# PowerDomain.net
KiCad netlist of a schematic drawn in Altium Designer
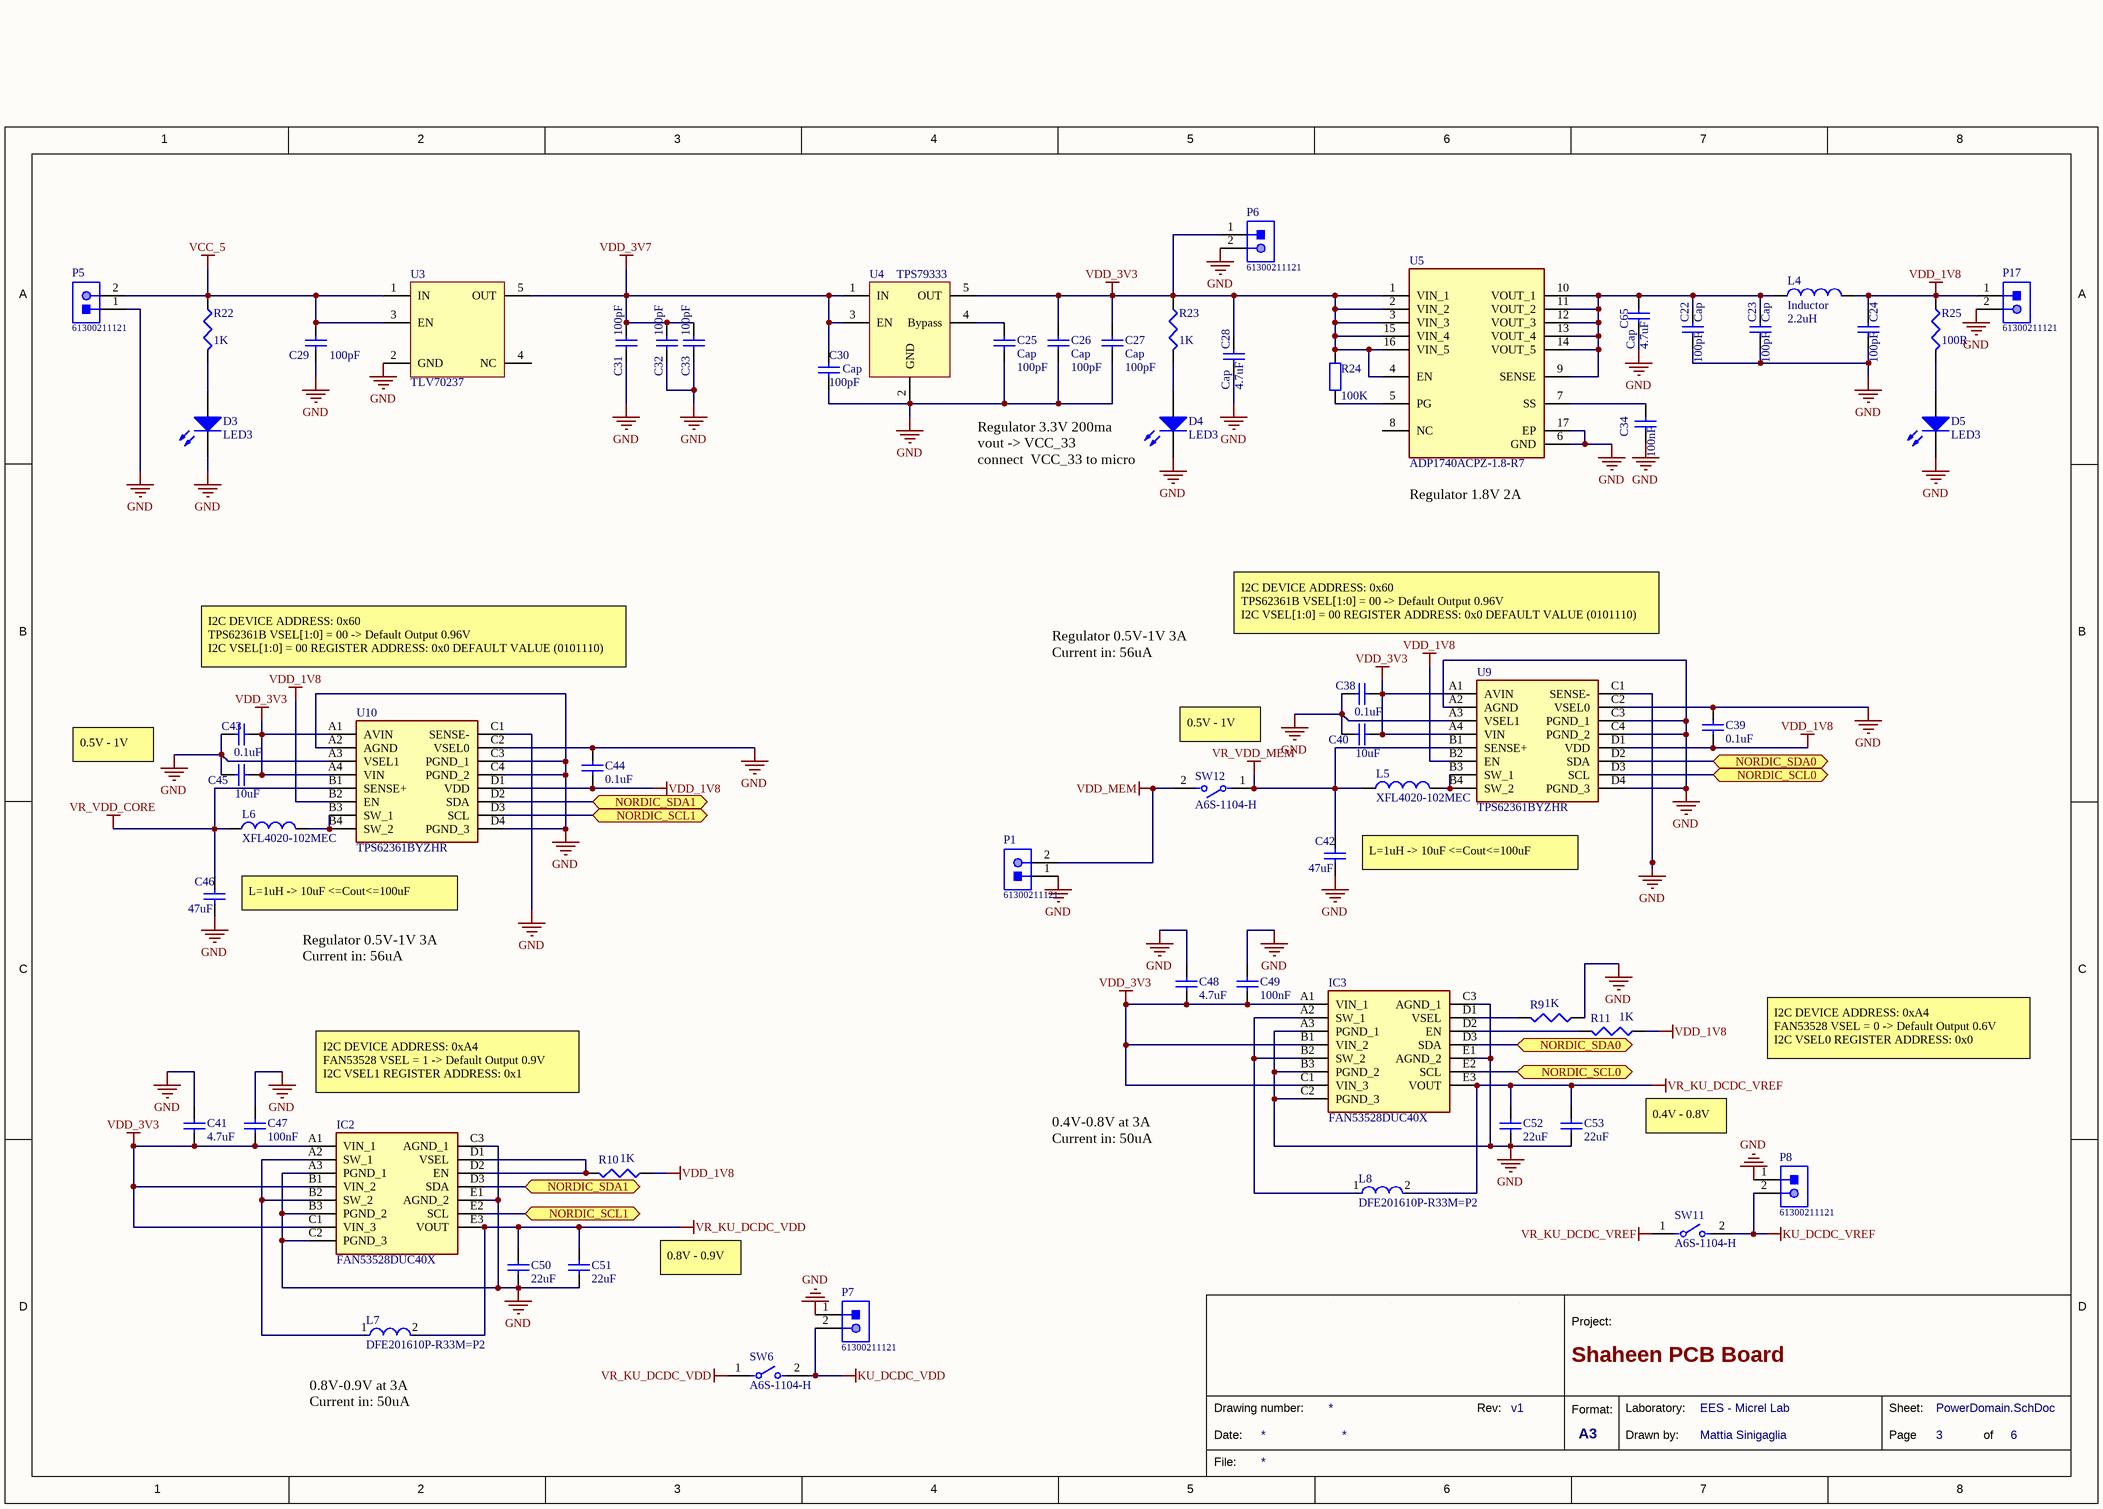
[diagram p0: PowerDomain.SchDoc]

(export (version "E")
  (design (tool "Eeschema 10.0.6"))
  (components
    (comp (ref "C22")
      (value "Cap")
      (footprint "0603")
      (description "Capacitor")
      (fields (field (name "ALTIUM_VALUE") "100pF") (field (name "PUBLISHER") "Altium Limited"))
      (libsource (lib "Miscellaneous Devices") (part "Cap"))
    )
    (comp (ref "C23")
      (value "Cap")
      (footprint "0603")
      (description "Capacitor")
      (fields (field (name "ALTIUM_VALUE") "100pF") (field (name "PUBLISHER") "Altium Limited"))
      (libsource (lib "Miscellaneous Devices") (part "Cap"))
    )
    (comp (ref "C24")
      (value "100pF")
      (footprint "0603")
      (description "Capacitor")
      (fields (field (name "Comment") "Cap") (field (name "PUBLISHER") "Altium Limited"))
      (libsource (lib "Miscellaneous Devices") (part "Cap"))
    )
    (comp (ref "C25")
      (value "Cap")
      (footprint "cap_0402_R - modified")
      (description "Capacitor")
      (fields (field (name "ALTIUM_VALUE") "100pF") (field (name "PUBLISHER") "Altium Limited"))
      (libsource (lib "Miscellaneous Devices") (part "Cap"))
    )
    (comp (ref "C26")
      (value "Cap")
      (footprint "cap_0402_R - modified")
      (description "Capacitor")
      (fields (field (name "ALTIUM_VALUE") "100pF") (field (name "PUBLISHER") "Altium Limited"))
      (libsource (lib "Miscellaneous Devices") (part "Cap"))
    )
    (comp (ref "C27")
      (value "Cap")
      (footprint "cap_0402_R - modified")
      (description "Capacitor")
      (fields (field (name "ALTIUM_VALUE") "100pF") (field (name "PUBLISHER") "Altium Limited"))
      (libsource (lib "Miscellaneous Devices") (part "Cap"))
    )
    (comp (ref "C28")
      (value "Cap")
      (footprint "0603")
      (description "Capacitor")
      (fields (field (name "ALTIUM_VALUE") "4.7uF") (field (name "PUBLISHER") "Altium Limited"))
      (libsource (lib "Miscellaneous Devices") (part "Cap"))
    )
    (comp (ref "C29")
      (value "100pF")
      (footprint "1608[0603]")
      (description "Capacitor (Semiconductor SIM Model)")
      (fields (field (name "Comment") "Cap Semi") (field (name "PUBLISHER") "Altium Limited"))
      (libsource (lib "Miscellaneous Devices") (part "Cap Semi"))
    )
    (comp (ref "C30")
      (value "Cap")
      (footprint "cap_0402_R - modified")
      (description "Capacitor")
      (fields (field (name "ALTIUM_VALUE") "100pF") (field (name "PUBLISHER") "Altium Limited"))
      (libsource (lib "Miscellaneous Devices") (part "Cap"))
    )
    (comp (ref "C31")
      (value "100pF")
      (footprint "1608[0603]")
      (description "Capacitor (Semiconductor SIM Model)")
      (fields (field (name "Comment") "Cap Semi") (field (name "PUBLISHER") "Altium Limited"))
      (libsource (lib "Miscellaneous Devices") (part "Cap Semi"))
    )
    (comp (ref "C32")
      (value "100pF")
      (footprint "1608[0603]")
      (description "Capacitor (Semiconductor SIM Model)")
      (fields (field (name "Comment") "Cap Semi") (field (name "PUBLISHER") "Altium Limited"))
      (libsource (lib "Miscellaneous Devices") (part "Cap Semi"))
    )
    (comp (ref "C33")
      (value "100pF")
      (footprint "1608[0603]")
      (description "Capacitor (Semiconductor SIM Model)")
      (fields (field (name "Comment") "Cap Semi") (field (name "PUBLISHER") "Altium Limited"))
      (libsource (lib "Miscellaneous Devices") (part "Cap Semi"))
    )
    (comp (ref "C34")
      (value "100nF")
      (footprint "0603")
      (description "Capacitor")
      (fields (field (name "PUBLISHER") "Altium Limited"))
      (libsource (lib "Miscellaneous Devices") (part "Cap"))
    )
    (comp (ref "C38")
      (value "0.1uF")
      (footprint "0603")
      (description "Capacitor")
      (fields (field (name "Comment") "Cap") (field (name "PUBLISHER") "Altium Limited"))
      (libsource (lib "Miscellaneous Devices") (part "Cap"))
    )
    (comp (ref "C39")
      (value "0.1uF")
      (footprint "0603")
      (description "Capacitor")
      (fields (field (name "Comment") "Cap") (field (name "PUBLISHER") "Altium Limited"))
      (libsource (lib "Miscellaneous Devices") (part "Cap"))
    )
    (comp (ref "C40")
      (value "10uF")
      (footprint "0603")
      (description "Capacitor")
      (fields (field (name "Comment") "Cap") (field (name "PUBLISHER") "Altium Limited"))
      (libsource (lib "Miscellaneous Devices") (part "Cap"))
    )
    (comp (ref "C41")
      (value "4.7uF")
      (footprint "0603")
      (description "Capacitor")
      (fields (field (name "Comment") "Cap") (field (name "PUBLISHER") "Altium Limited"))
      (libsource (lib "Miscellaneous Devices") (part "Cap"))
    )
    (comp (ref "C42")
      (value "47uF")
      (footprint "0603")
      (description "Capacitor")
      (fields (field (name "Comment") "Cap") (field (name "PUBLISHER") "Altium Limited"))
      (libsource (lib "Miscellaneous Devices") (part "Cap"))
    )
    (comp (ref "C43")
      (value "0.1uF")
      (footprint "0603")
      (description "Capacitor")
      (fields (field (name "Comment") "Cap") (field (name "PUBLISHER") "Altium Limited"))
      (libsource (lib "Miscellaneous Devices") (part "Cap"))
    )
    (comp (ref "C44")
      (value "0.1uF")
      (footprint "0603")
      (description "Capacitor")
      (fields (field (name "Comment") "Cap") (field (name "PUBLISHER") "Altium Limited"))
      (libsource (lib "Miscellaneous Devices") (part "Cap"))
    )
    (comp (ref "C45")
      (value "10uF")
      (footprint "0603")
      (description "Capacitor")
      (fields (field (name "Comment") "Cap") (field (name "PUBLISHER") "Altium Limited"))
      (libsource (lib "Miscellaneous Devices") (part "Cap"))
    )
    (comp (ref "C46")
      (value "47uF")
      (footprint "0603")
      (description "Capacitor")
      (fields (field (name "Comment") "Cap") (field (name "PUBLISHER") "Altium Limited"))
      (libsource (lib "Miscellaneous Devices") (part "Cap"))
    )
    (comp (ref "C47")
      (value "100nF")
      (footprint "0603")
      (description "Capacitor")
      (fields (field (name "Comment") "Cap") (field (name "PUBLISHER") "Altium Limited"))
      (libsource (lib "Miscellaneous Devices") (part "Cap"))
    )
    (comp (ref "C48")
      (value "4.7uF")
      (footprint "0603")
      (description "Capacitor")
      (fields (field (name "Comment") "Cap") (field (name "PUBLISHER") "Altium Limited"))
      (libsource (lib "Miscellaneous Devices") (part "Cap"))
    )
    (comp (ref "C49")
      (value "100nF")
      (footprint "0603")
      (description "Capacitor")
      (fields (field (name "Comment") "Cap") (field (name "PUBLISHER") "Altium Limited"))
      (libsource (lib "Miscellaneous Devices") (part "Cap"))
    )
    (comp (ref "C50")
      (value "22uF")
      (footprint "0603")
      (description "Capacitor")
      (fields (field (name "Comment") "Cap") (field (name "PUBLISHER") "Altium Limited"))
      (libsource (lib "Miscellaneous Devices") (part "Cap"))
    )
    (comp (ref "C51")
      (value "22uF")
      (footprint "0603")
      (description "Capacitor")
      (fields (field (name "Comment") "Cap") (field (name "PUBLISHER") "Altium Limited"))
      (libsource (lib "Miscellaneous Devices") (part "Cap"))
    )
    (comp (ref "C52")
      (value "22uF")
      (footprint "0603")
      (description "Capacitor")
      (fields (field (name "Comment") "Cap") (field (name "PUBLISHER") "Altium Limited"))
      (libsource (lib "Miscellaneous Devices") (part "Cap"))
    )
    (comp (ref "C53")
      (value "22uF")
      (footprint "0603")
      (description "Capacitor")
      (fields (field (name "Comment") "Cap") (field (name "PUBLISHER") "Altium Limited"))
      (libsource (lib "Miscellaneous Devices") (part "Cap"))
    )
    (comp (ref "C65")
      (value "Cap")
      (footprint "0603")
      (description "Capacitor")
      (fields (field (name "ALTIUM_VALUE") "4.7uF") (field (name "PUBLISHER") "Altium Limited"))
      (libsource (lib "Miscellaneous Devices") (part "Cap"))
    )
    (comp (ref "D3")
      (value "LED3")
      (footprint "0603")
      (description "Typical BLUE SiC LED")
      (fields (field (name "PUBLISHER") "Altium Limited"))
      (libsource (lib "Miscellaneous Devices") (part "LED3"))
    )
    (comp (ref "D4")
      (value "LED3")
      (footprint "0603")
      (description "Typical BLUE SiC LED")
      (fields (field (name "PUBLISHER") "Altium Limited"))
      (libsource (lib "Miscellaneous Devices") (part "LED3"))
    )
    (comp (ref "D5")
      (value "LED3")
      (footprint "0603")
      (description "Typical BLUE SiC LED")
      (fields (field (name "PUBLISHER") "Altium Limited"))
      (libsource (lib "Miscellaneous Devices") (part "LED3"))
    )
    (comp (ref "IC2")
      (value "FAN53528DUC40X")
      (footprint "BGA15C40P3X5_131X202X62")
      (description "Integrated Circuit")
      (libsource (lib "FAN53528DUC40X") (part "FAN53528DUC40X"))
    )
    (comp (ref "IC3")
      (value "FAN53528DUC40X")
      (footprint "BGA15C40P3X5_131X202X62")
      (description "Integrated Circuit")
      (libsource (lib "FAN53528DUC40X") (part "FAN53528DUC40X"))
    )
    (comp (ref "L4")
      (value "Inductor")
      (footprint "Demo_Board_library_PCB:0603")
      (fields (field (name "ALTIUM_VALUE") "2.2uH") (field (name "PUBLISHER") "Altium Limited"))
      (libsource (lib "Miscellaneous Devices") (part "Inductor"))
    )
    (comp (ref "L5")
      (value "XFL4020-102MEC")
      (footprint "COIL-XFL4020_V")
      (description "Shielded Power Inductor, 1 uH, 64 MHz, -40 to 125 degC, 2-Pin SMD, RoHS, Tape and Reel")
      (fields (field (name "MANUFACTURER") "Coilcraft") (field (name "TOLERANCE") "20%"))
      (libsource (lib "Altium Content Vault") (part "IND-2"))
    )
    (comp (ref "L6")
      (value "XFL4020-102MEC")
      (footprint "COIL-XFL4020_V")
      (description "Shielded Power Inductor, 1 uH, 64 MHz, -40 to 125 degC, 2-Pin SMD, RoHS, Tape and Reel")
      (fields (field (name "MANUFACTURER") "Coilcraft") (field (name "TOLERANCE") "20%"))
      (libsource (lib "Altium Content Vault") (part "IND-2"))
    )
    (comp (ref "L7")
      (value "DFE201610P-R33M=P2")
      (footprint "FP-DFE201610C-MFG")
      (description "Shielded Wirewound Inductor 0.33uH 20% 3500mA 0.034Ω 0806 (2016)")
      (fields (field (name "TOLERANCE") "20%"))
      (libsource (lib "Altium Content Vault") (part "725321dda6339637d4d059423bc1c3c"))
    )
    (comp (ref "L8")
      (value "DFE201610P-R33M=P2")
      (footprint "FP-DFE201610C-MFG")
      (description "Shielded Wirewound Inductor 0.33uH 20% 3500mA 0.034Ω 0806 (2016)")
      (fields (field (name "TOLERANCE") "20%"))
      (libsource (lib "Altium Content Vault") (part "725321dda6339637d4d059423bc1c3c"))
    )
    (comp (ref "P1")
      (value "61300211121")
      (footprint "61300211121")
      (description "THT Vertical Pin Header WR-PHD, Pitch 2.54 mm, Single Row, 2 pins")
      (fields (field (name "MANUFACTURER") "Wurth Elektronik") (field (name "PUBLISHER") "WurthElektronik"))
      (libsource (lib "") (part "WE-CN-1P-M-R2_1"))
    )
    (comp (ref "P5")
      (value "61300211121")
      (footprint "61300211121")
      (description "THT Vertical Pin Header WR-PHD, Pitch 2.54 mm, Single Row, 2 pins")
      (fields (field (name "MANUFACTURER") "Wurth Elektronik") (field (name "PUBLISHER") "WurthElektronik"))
      (libsource (lib "") (part "WE-CN-1P-M-R2_1"))
    )
    (comp (ref "P6")
      (value "61300211121")
      (footprint "61300211121")
      (description "THT Vertical Pin Header WR-PHD, Pitch 2.54 mm, Single Row, 2 pins")
      (fields (field (name "MANUFACTURER") "Wurth Elektronik") (field (name "PUBLISHER") "WurthElektronik"))
      (libsource (lib "Altium Content Vault") (part "WE-CN-1P-M-R2"))
    )
    (comp (ref "P7")
      (value "61300211121")
      (footprint "61300211121")
      (description "THT Vertical Pin Header WR-PHD, Pitch 2.54 mm, Single Row, 2 pins")
      (fields (field (name "MANUFACTURER") "Wurth Elektronik") (field (name "PUBLISHER") "WurthElektronik"))
      (libsource (lib "Altium Content Vault") (part "WE-CN-1P-M-R2"))
    )
    (comp (ref "P8")
      (value "61300211121")
      (footprint "61300211121")
      (description "THT Vertical Pin Header WR-PHD, Pitch 2.54 mm, Single Row, 2 pins")
      (fields (field (name "MANUFACTURER") "Wurth Elektronik") (field (name "PUBLISHER") "WurthElektronik"))
      (libsource (lib "Altium Content Vault") (part "WE-CN-1P-M-R2"))
    )
    (comp (ref "P17")
      (value "61300211121")
      (footprint "61300211121")
      (description "THT Vertical Pin Header WR-PHD, Pitch 2.54 mm, Single Row, 2 pins")
      (fields (field (name "MANUFACTURER") "Wurth Elektronik") (field (name "PUBLISHER") "WurthElektronik"))
      (libsource (lib "Altium Content Vault") (part "WE-CN-1P-M-R2"))
    )
    (comp (ref "R9")
      (value "1K")
      (footprint "J1-0603")
      (description "Resistor")
      (fields (field (name "Comment") "0R") (field (name "PUBLISHER") "Altium Limited"))
      (libsource (lib "Miscellaneous Devices") (part "Res3"))
    )
    (comp (ref "R10")
      (value "1K")
      (footprint "J1-0603")
      (description "Resistor")
      (fields (field (name "Comment") "0R") (field (name "PUBLISHER") "Altium Limited"))
      (libsource (lib "Miscellaneous Devices") (part "Res3"))
    )
    (comp (ref "R11")
      (value "1K")
      (footprint "J1-0603")
      (description "Resistor")
      (fields (field (name "Comment") "0R") (field (name "PUBLISHER") "Altium Limited"))
      (libsource (lib "Miscellaneous Devices") (part "Res3"))
    )
    (comp (ref "R22")
      (value "1K")
      (footprint "res_0402_R - modified")
      (description "Resistor")
      (fields (field (name "Comment") "Res3") (field (name "PUBLISHER") "Altium Limited"))
      (libsource (lib "Miscellaneous Devices") (part "Res3"))
    )
    (comp (ref "R23")
      (value "1K")
      (footprint "res_0402_R - modified")
      (description "Resistor")
      (fields (field (name "Comment") "Res3") (field (name "PUBLISHER") "Altium Limited"))
      (libsource (lib "Miscellaneous Devices") (part "Res3"))
    )
    (comp (ref "R24")
      (value "100K")
      (footprint "0603")
      (description "Resistor")
      (fields (field (name "PUBLISHER") "Altium Limited"))
      (libsource (lib "Miscellaneous Devices") (part "Res2"))
    )
    (comp (ref "R25")
      (value "100R")
      (footprint "res_0402_R - modified")
      (description "Resistor")
      (fields (field (name "Comment") "Res3") (field (name "PUBLISHER") "Altium Limited"))
      (libsource (lib "Miscellaneous Devices") (part "Res3"))
    )
    (comp (ref "SW6")
      (value "A6S-1104-H")
      (footprint "FP-A6S-1104-H-MFG")
      (description "SWITCH SLIDE DIP SPST 25MA 24V")
      (fields
        (field (name "MANUFACTURER") "Omron Electronics Inc-EMC Div")
        (field (name "OCTOPART") "https://octopart.com/a6s-1104-h-omron-55410938")
      )
      (libsource (lib "Altium Content Vault") (part "bb27bde45df87f1f469753f287ef5ae"))
    )
    (comp (ref "SW11")
      (value "A6S-1104-H")
      (footprint "FP-A6S-1104-H-MFG")
      (description "SWITCH SLIDE DIP SPST 25MA 24V")
      (fields
        (field (name "MANUFACTURER") "Omron Electronics Inc-EMC Div")
        (field (name "OCTOPART") "https://octopart.com/a6s-1104-h-omron-55410938")
      )
      (libsource (lib "Altium Content Vault") (part "bb27bde45df87f1f469753f287ef5ae"))
    )
    (comp (ref "SW12")
      (value "A6S-1104-H")
      (footprint "FP-A6S-1104-H-MFG")
      (description "SWITCH SLIDE DIP SPST 25MA 24V")
      (fields
        (field (name "MANUFACTURER") "Omron Electronics Inc-EMC Div")
        (field (name "OCTOPART") "https://octopart.com/a6s-1104-h-omron-55410938")
      )
      (libsource (lib "Altium Content Vault") (part "bb27bde45df87f1f469753f287ef5ae"))
    )
    (comp (ref "U3")
      (value "TLV70237")
      (footprint "Demo_Board_library_PCB:SOT23__DDC__(R - PDSO-  G5)")
      (description "Linear Regulator")
      (libsource (lib "Demo_Board_library_SCH") (part "TLV70237"))
    )
    (comp (ref "U4")
      (value "TPS79333")
      (footprint "Demo_Board_library_PCB:SOT_23__DBV_(R - PDSO - G5)")
      (description "Regulator")
      (libsource (lib "Demo_Board_library_SCH") (part "TPS79333"))
    )
    (comp (ref "U5")
      (value "ADP1740ACPZ-1.8-R7")
      (footprint "ADP1740ACPZ-1.8-R7")
      (description "LDO Voltage Regulators 2A LDO Fix V-out Family")
      (fields (field (name "MOUSER PART NUMBER") "584-ADP1740ACPZ1.8R7"))
      (libsource (lib "ADP1740ACPZ-1.8-R7") (part "ADP1740ACPZ-1.8-R7"))
    )
    (comp (ref "U9")
      (value "TPS62361BYZHR")
      (footprint "BGA16C50P4X4_206X206X62")
      (description "Integrated Circuit")
      (libsource (lib "TPS62361BYZHR") (part "TPS62361BYZHR"))
    )
    (comp (ref "U10")
      (value "TPS62361BYZHR")
      (footprint "BGA16C50P4X4_206X206X62")
      (description "Integrated Circuit")
      (libsource (lib "TPS62361BYZHR") (part "TPS62361BYZHR"))
    )
  )
  (nets
    (net (code "1") (name "/NORDIC_SCL0") (class "Default")
      (node (ref "IC3") (pin "E2") (pinfunction "SCL_E2") (pintype "passive"))
      (node (ref "U9") (pin "D3") (pinfunction "SCL_D3") (pintype "passive"))
    )
    (net (code "2") (name "/NORDIC_SCL1") (class "Default")
      (node (ref "IC2") (pin "E2") (pinfunction "SCL_E2") (pintype "passive"))
      (node (ref "U10") (pin "D3") (pinfunction "SCL_D3") (pintype "passive"))
    )
    (net (code "3") (name "/NORDIC_SDA0") (class "Default")
      (node (ref "IC3") (pin "D3") (pinfunction "SDA_D3") (pintype "passive"))
      (node (ref "U9") (pin "D2") (pinfunction "SDA_D2") (pintype "passive"))
    )
    (net (code "4") (name "/NORDIC_SDA1") (class "Default")
      (node (ref "IC2") (pin "D3") (pinfunction "SDA_D3") (pintype "passive"))
      (node (ref "U10") (pin "D2") (pinfunction "SDA_D2") (pintype "passive"))
    )
    (net (code "5") (name "GND") (class "Default")
      (node (ref "C22") (pin "2") (pinfunction "2_2") (pintype "passive"))
      (node (ref "C23") (pin "2") (pinfunction "2_2") (pintype "passive"))
      (node (ref "C24") (pin "2") (pinfunction "2_2") (pintype "passive"))
      (node (ref "C25") (pin "1") (pinfunction "1_1") (pintype "passive"))
      (node (ref "C26") (pin "2") (pinfunction "2_2") (pintype "passive"))
      (node (ref "C27") (pin "1") (pinfunction "1_1") (pintype "passive"))
      (node (ref "C28") (pin "2") (pinfunction "2_2") (pintype "passive"))
      (node (ref "C29") (pin "1") (pinfunction "1_1") (pintype "passive"))
      (node (ref "C30") (pin "1") (pinfunction "1_1") (pintype "passive"))
      (node (ref "C31") (pin "1") (pinfunction "1_1") (pintype "passive"))
      (node (ref "C32") (pin "1") (pinfunction "1_1") (pintype "passive"))
      (node (ref "C33") (pin "1") (pinfunction "1_1") (pintype "passive"))
      (node (ref "C34") (pin "2") (pinfunction "2_2") (pintype "passive"))
      (node (ref "C38") (pin "1") (pinfunction "1_1") (pintype "passive"))
      (node (ref "C39") (pin "1") (pinfunction "1_1") (pintype "passive"))
      (node (ref "C40") (pin "2") (pinfunction "2_2") (pintype "passive"))
      (node (ref "C41") (pin "1") (pinfunction "1_1") (pintype "passive"))
      (node (ref "C42") (pin "2") (pinfunction "2_2") (pintype "passive"))
      (node (ref "C43") (pin "1") (pinfunction "1_1") (pintype "passive"))
      (node (ref "C44") (pin "1") (pinfunction "1_1") (pintype "passive"))
      (node (ref "C45") (pin "2") (pinfunction "2_2") (pintype "passive"))
      (node (ref "C46") (pin "2") (pinfunction "2_2") (pintype "passive"))
      (node (ref "C47") (pin "1") (pinfunction "1_1") (pintype "passive"))
      (node (ref "C48") (pin "1") (pinfunction "1_1") (pintype "passive"))
      (node (ref "C49") (pin "1") (pinfunction "1_1") (pintype "passive"))
      (node (ref "C50") (pin "2") (pinfunction "2_2") (pintype "passive"))
      (node (ref "C51") (pin "2") (pinfunction "2_2") (pintype "passive"))
      (node (ref "C52") (pin "2") (pinfunction "2_2") (pintype "passive"))
      (node (ref "C53") (pin "2") (pinfunction "2_2") (pintype "passive"))
      (node (ref "C65") (pin "2") (pinfunction "2_2") (pintype "passive"))
      (node (ref "D3") (pin "2") (pinfunction "K_2") (pintype "passive"))
      (node (ref "D4") (pin "2") (pinfunction "K_2") (pintype "passive"))
      (node (ref "D5") (pin "2") (pinfunction "K_2") (pintype "passive"))
      (node (ref "IC2") (pin "A3") (pinfunction "PGND_1_A3") (pintype "passive"))
      (node (ref "IC2") (pin "B3") (pinfunction "PGND_2_B3") (pintype "passive"))
      (node (ref "IC2") (pin "C2") (pinfunction "PGND_3_C2") (pintype "passive"))
      (node (ref "IC2") (pin "C3") (pinfunction "AGND_1_C3") (pintype "passive"))
      (node (ref "IC2") (pin "E1") (pinfunction "AGND_2_E1") (pintype "passive"))
      (node (ref "IC3") (pin "A3") (pinfunction "PGND_1_A3") (pintype "passive"))
      (node (ref "IC3") (pin "B3") (pinfunction "PGND_2_B3") (pintype "passive"))
      (node (ref "IC3") (pin "C2") (pinfunction "PGND_3_C2") (pintype "passive"))
      (node (ref "IC3") (pin "C3") (pinfunction "AGND_1_C3") (pintype "passive"))
      (node (ref "IC3") (pin "E1") (pinfunction "AGND_2_E1") (pintype "passive"))
      (node (ref "P1") (pin "1") (pinfunction "1_1") (pintype "passive"))
      (node (ref "P17") (pin "2") (pinfunction "2_2") (pintype "passive"))
      (node (ref "P5") (pin "1") (pinfunction "1_1") (pintype "passive"))
      (node (ref "P6") (pin "2") (pinfunction "2_2") (pintype "passive"))
      (node (ref "P7") (pin "1") (pinfunction "1_1") (pintype "passive"))
      (node (ref "P8") (pin "1") (pinfunction "1_1") (pintype "passive"))
      (node (ref "R9") (pin "2") (pinfunction "2_2") (pintype "passive"))
      (node (ref "U10") (pin "A2") (pinfunction "AGND_A2") (pintype "passive"))
      (node (ref "U10") (pin "A3") (pinfunction "VSEL1_A3") (pintype "passive"))
      (node (ref "U10") (pin "C1") (pinfunction "SENSE-_C1") (pintype "passive"))
      (node (ref "U10") (pin "C2") (pinfunction "VSEL0_C2") (pintype "passive"))
      (node (ref "U10") (pin "C3") (pinfunction "PGND_1_C3") (pintype "passive"))
      (node (ref "U10") (pin "C4") (pinfunction "PGND_2_C4") (pintype "passive"))
      (node (ref "U10") (pin "D4") (pinfunction "PGND_3_D4") (pintype "passive"))
      (node (ref "U3") (pin "2") (pinfunction "GND_2") (pintype "passive"))
      (node (ref "U4") (pin "2") (pinfunction "GND_2") (pintype "passive"))
      (node (ref "U5") (pin "17") (pinfunction "EP_17") (pintype "passive"))
      (node (ref "U5") (pin "6") (pinfunction "GND_6") (pintype "passive"))
      (node (ref "U9") (pin "A2") (pinfunction "AGND_A2") (pintype "passive"))
      (node (ref "U9") (pin "A3") (pinfunction "VSEL1_A3") (pintype "passive"))
      (node (ref "U9") (pin "C1") (pinfunction "SENSE-_C1") (pintype "passive"))
      (node (ref "U9") (pin "C2") (pinfunction "VSEL0_C2") (pintype "passive"))
      (node (ref "U9") (pin "C3") (pinfunction "PGND_1_C3") (pintype "passive"))
      (node (ref "U9") (pin "C4") (pinfunction "PGND_2_C4") (pintype "passive"))
      (node (ref "U9") (pin "D4") (pinfunction "PGND_3_D4") (pintype "passive"))
    )
    (net (code "6") (name "KU_DCDC_VDD") (class "Default")
      (node (ref "P7") (pin "2") (pinfunction "2_2") (pintype "passive"))
      (node (ref "SW6") (pin "2") (pinfunction "2_2") (pintype "passive"))
    )
    (net (code "7") (name "KU_DCDC_VREF") (class "Default")
      (node (ref "P8") (pin "2") (pinfunction "2_2") (pintype "passive"))
      (node (ref "SW11") (pin "2") (pinfunction "2_2") (pintype "passive"))
    )
    (net (code "8") (name "Net-(D3-A)") (class "Default")
      (node (ref "D3") (pin "1") (pinfunction "A_1") (pintype "passive"))
      (node (ref "R22") (pin "2") (pinfunction "2_2") (pintype "passive"))
    )
    (net (code "9") (name "Net-(D4-A)") (class "Default")
      (node (ref "D4") (pin "1") (pinfunction "A_1") (pintype "passive"))
      (node (ref "R23") (pin "2") (pinfunction "2_2") (pintype "passive"))
    )
    (net (code "10") (name "Net-(D5-A)") (class "Default")
      (node (ref "D5") (pin "1") (pinfunction "A_1") (pintype "passive"))
      (node (ref "R25") (pin "2") (pinfunction "2_2") (pintype "passive"))
    )
    (net (code "11") (name "Net-(IC2-EN)") (class "Default")
      (node (ref "IC2") (pin "D1") (pinfunction "VSEL_D1") (pintype "passive"))
      (node (ref "IC2") (pin "D2") (pinfunction "EN_D2") (pintype "passive"))
      (node (ref "R10") (pin "1") (pinfunction "1_1") (pintype "passive"))
    )
    (net (code "12") (name "Net-(IC2-SW_1)") (class "Default")
      (node (ref "IC2") (pin "A2") (pinfunction "SW_1_A2") (pintype "passive"))
      (node (ref "IC2") (pin "B2") (pinfunction "SW_2_B2") (pintype "passive"))
      (node (ref "L7") (pin "1") (pinfunction "1_1") (pintype "passive"))
    )
    (net (code "13") (name "Net-(IC3-EN)") (class "Default")
      (node (ref "IC3") (pin "D2") (pinfunction "EN_D2") (pintype "passive"))
      (node (ref "R11") (pin "1") (pinfunction "1_1") (pintype "passive"))
    )
    (net (code "14") (name "Net-(IC3-SW_1)") (class "Default")
      (node (ref "IC3") (pin "A2") (pinfunction "SW_1_A2") (pintype "passive"))
      (node (ref "IC3") (pin "B2") (pinfunction "SW_2_B2") (pintype "passive"))
      (node (ref "L8") (pin "1") (pinfunction "1_1") (pintype "passive"))
    )
    (net (code "15") (name "Net-(IC3-VSEL)") (class "Default")
      (node (ref "IC3") (pin "D1") (pinfunction "VSEL_D1") (pintype "passive"))
      (node (ref "R9") (pin "1") (pinfunction "1_1") (pintype "passive"))
    )
    (net (code "16") (name "Net-(U4-Bypass)") (class "Default")
      (node (ref "C25") (pin "2") (pinfunction "2_2") (pintype "passive"))
      (node (ref "U4") (pin "4") (pinfunction "Bypass_4") (pintype "passive"))
    )
    (net (code "17") (name "Net-(U5-PG)") (class "Default")
      (node (ref "R24") (pin "1") (pinfunction "1_1") (pintype "passive"))
      (node (ref "U5") (pin "5") (pinfunction "PG_5") (pintype "passive"))
    )
    (net (code "18") (name "Net-(U5-SENSE)") (class "Default")
      (node (ref "C22") (pin "1") (pinfunction "1_1") (pintype "passive"))
      (node (ref "C23") (pin "1") (pinfunction "1_1") (pintype "passive"))
      (node (ref "C65") (pin "1") (pinfunction "1_1") (pintype "passive"))
      (node (ref "L4") (pin "1") (pinfunction "1_1") (pintype "passive"))
      (node (ref "U5") (pin "10") (pinfunction "VOUT_1_10") (pintype "passive"))
      (node (ref "U5") (pin "11") (pinfunction "VOUT_2_11") (pintype "passive"))
      (node (ref "U5") (pin "12") (pinfunction "VOUT_3_12") (pintype "passive"))
      (node (ref "U5") (pin "13") (pinfunction "VOUT_4_13") (pintype "passive"))
      (node (ref "U5") (pin "14") (pinfunction "VOUT_5_14") (pintype "passive"))
      (node (ref "U5") (pin "9") (pinfunction "SENSE_9") (pintype "passive"))
    )
    (net (code "19") (name "Net-(U5-SS)") (class "Default")
      (node (ref "C34") (pin "1") (pinfunction "1_1") (pintype "passive"))
      (node (ref "U5") (pin "7") (pinfunction "SS_7") (pintype "passive"))
    )
    (net (code "20") (name "Net-(U9-SW_1)") (class "Default")
      (node (ref "L5") (pin "2") (pinfunction "2_2") (pintype "passive"))
      (node (ref "U9") (pin "B3") (pinfunction "SW_1_B3") (pintype "passive"))
      (node (ref "U9") (pin "B4") (pinfunction "SW_2_B4") (pintype "passive"))
    )
    (net (code "21") (name "Net-(U10-SW_1)") (class "Default")
      (node (ref "L6") (pin "2") (pinfunction "2_2") (pintype "passive"))
      (node (ref "U10") (pin "B3") (pinfunction "SW_1_B3") (pintype "passive"))
      (node (ref "U10") (pin "B4") (pinfunction "SW_2_B4") (pintype "passive"))
    )
    (net (code "22") (name "VCC_5") (class "Default")
      (node (ref "C29") (pin "2") (pinfunction "2_2") (pintype "passive"))
      (node (ref "P5") (pin "2") (pinfunction "2_2") (pintype "passive"))
      (node (ref "R22") (pin "1") (pinfunction "1_1") (pintype "passive"))
      (node (ref "U3") (pin "1") (pinfunction "IN_1") (pintype "passive"))
      (node (ref "U3") (pin "3") (pinfunction "EN_3") (pintype "passive"))
    )
    (net (code "23") (name "VDD_1V8") (class "Default")
      (node (ref "C24") (pin "1") (pinfunction "1_1") (pintype "passive"))
      (node (ref "C39") (pin "2") (pinfunction "2_2") (pintype "passive"))
      (node (ref "C44") (pin "2") (pinfunction "2_2") (pintype "passive"))
      (node (ref "L4") (pin "2") (pinfunction "2_2") (pintype "passive"))
      (node (ref "P17") (pin "1") (pinfunction "1_1") (pintype "passive"))
      (node (ref "R10") (pin "2") (pinfunction "2_2") (pintype "passive"))
      (node (ref "R11") (pin "2") (pinfunction "2_2") (pintype "passive"))
      (node (ref "R25") (pin "1") (pinfunction "1_1") (pintype "passive"))
      (node (ref "U10") (pin "B2") (pinfunction "EN_B2") (pintype "passive"))
      (node (ref "U10") (pin "D1") (pinfunction "VDD_D1") (pintype "passive"))
      (node (ref "U9") (pin "B2") (pinfunction "EN_B2") (pintype "passive"))
      (node (ref "U9") (pin "D1") (pinfunction "VDD_D1") (pintype "passive"))
    )
    (net (code "24") (name "VDD_3V3") (class "Default")
      (node (ref "C26") (pin "1") (pinfunction "1_1") (pintype "passive"))
      (node (ref "C27") (pin "2") (pinfunction "2_2") (pintype "passive"))
      (node (ref "C28") (pin "1") (pinfunction "1_1") (pintype "passive"))
      (node (ref "C38") (pin "2") (pinfunction "2_2") (pintype "passive"))
      (node (ref "C40") (pin "1") (pinfunction "1_1") (pintype "passive"))
      (node (ref "C41") (pin "2") (pinfunction "2_2") (pintype "passive"))
      (node (ref "C43") (pin "2") (pinfunction "2_2") (pintype "passive"))
      (node (ref "C45") (pin "1") (pinfunction "1_1") (pintype "passive"))
      (node (ref "C47") (pin "2") (pinfunction "2_2") (pintype "passive"))
      (node (ref "C48") (pin "2") (pinfunction "2_2") (pintype "passive"))
      (node (ref "C49") (pin "2") (pinfunction "2_2") (pintype "passive"))
      (node (ref "IC2") (pin "A1") (pinfunction "VIN_1_A1") (pintype "passive"))
      (node (ref "IC2") (pin "B1") (pinfunction "VIN_2_B1") (pintype "passive"))
      (node (ref "IC2") (pin "C1") (pinfunction "VIN_3_C1") (pintype "passive"))
      (node (ref "IC3") (pin "A1") (pinfunction "VIN_1_A1") (pintype "passive"))
      (node (ref "IC3") (pin "B1") (pinfunction "VIN_2_B1") (pintype "passive"))
      (node (ref "IC3") (pin "C1") (pinfunction "VIN_3_C1") (pintype "passive"))
      (node (ref "P6") (pin "1") (pinfunction "1_1") (pintype "passive"))
      (node (ref "R23") (pin "1") (pinfunction "1_1") (pintype "passive"))
      (node (ref "R24") (pin "2") (pinfunction "2_2") (pintype "passive"))
      (node (ref "U10") (pin "A1") (pinfunction "AVIN_A1") (pintype "passive"))
      (node (ref "U10") (pin "A4") (pinfunction "VIN_A4") (pintype "passive"))
      (node (ref "U4") (pin "5") (pinfunction "OUT_5") (pintype "passive"))
      (node (ref "U5") (pin "1") (pinfunction "VIN_1_1") (pintype "passive"))
      (node (ref "U5") (pin "15") (pinfunction "VIN_4_15") (pintype "passive"))
      (node (ref "U5") (pin "16") (pinfunction "VIN_5_16") (pintype "passive"))
      (node (ref "U5") (pin "2") (pinfunction "VIN_2_2") (pintype "passive"))
      (node (ref "U5") (pin "3") (pinfunction "VIN_3_3") (pintype "passive"))
      (node (ref "U5") (pin "4") (pinfunction "EN_4") (pintype "passive"))
      (node (ref "U9") (pin "A1") (pinfunction "AVIN_A1") (pintype "passive"))
      (node (ref "U9") (pin "A4") (pinfunction "VIN_A4") (pintype "passive"))
    )
    (net (code "25") (name "VDD_3V7") (class "Default")
      (node (ref "C30") (pin "2") (pinfunction "2_2") (pintype "passive"))
      (node (ref "C31") (pin "2") (pinfunction "2_2") (pintype "passive"))
      (node (ref "C32") (pin "2") (pinfunction "2_2") (pintype "passive"))
      (node (ref "C33") (pin "2") (pinfunction "2_2") (pintype "passive"))
      (node (ref "U3") (pin "5") (pinfunction "OUT_5") (pintype "passive"))
      (node (ref "U4") (pin "1") (pinfunction "IN_1") (pintype "passive"))
      (node (ref "U4") (pin "3") (pinfunction "EN_3") (pintype "passive"))
    )
    (net (code "26") (name "VDD_MEM") (class "Default")
      (node (ref "P1") (pin "2") (pinfunction "2_2") (pintype "passive"))
      (node (ref "SW12") (pin "2") (pinfunction "2_2") (pintype "passive"))
    )
    (net (code "27") (name "VR_KU_DCDC_VDD") (class "Default")
      (node (ref "C50") (pin "1") (pinfunction "1_1") (pintype "passive"))
      (node (ref "C51") (pin "1") (pinfunction "1_1") (pintype "passive"))
      (node (ref "IC2") (pin "E3") (pinfunction "VOUT_E3") (pintype "passive"))
      (node (ref "L7") (pin "2") (pinfunction "2_2") (pintype "passive"))
      (node (ref "SW6") (pin "1") (pinfunction "1_1") (pintype "passive"))
    )
    (net (code "28") (name "VR_KU_DCDC_VREF") (class "Default")
      (node (ref "C52") (pin "1") (pinfunction "1_1") (pintype "passive"))
      (node (ref "C53") (pin "1") (pinfunction "1_1") (pintype "passive"))
      (node (ref "IC3") (pin "E3") (pinfunction "VOUT_E3") (pintype "passive"))
      (node (ref "L8") (pin "2") (pinfunction "2_2") (pintype "passive"))
      (node (ref "SW11") (pin "1") (pinfunction "1_1") (pintype "passive"))
    )
    (net (code "29") (name "VR_VDD_CORE") (class "Default")
      (node (ref "C46") (pin "1") (pinfunction "1_1") (pintype "passive"))
      (node (ref "L6") (pin "1") (pinfunction "1_1") (pintype "passive"))
      (node (ref "U10") (pin "B1") (pinfunction "SENSE+_B1") (pintype "passive"))
    )
    (net (code "30") (name "VR_VDD_MEM") (class "Default")
      (node (ref "C42") (pin "1") (pinfunction "1_1") (pintype "passive"))
      (node (ref "L5") (pin "1") (pinfunction "1_1") (pintype "passive"))
      (node (ref "SW12") (pin "1") (pinfunction "1_1") (pintype "passive"))
      (node (ref "U9") (pin "B1") (pinfunction "SENSE+_B1") (pintype "passive"))
    )
    (net (code "31") (name "unconnected-(U3-NC-Pad4)") (class "Default")
      (node (ref "U3") (pin "4") (pinfunction "NC_4") (pintype "passive"))
    )
    (net (code "32") (name "unconnected-(U5-NC-Pad8)") (class "Default")
      (node (ref "U5") (pin "8") (pinfunction "NC_8") (pintype "passive"))
    )
  )
)
